# WS2811ControlBoard.net
KiCad netlist of a schematic drawn in EAGLE
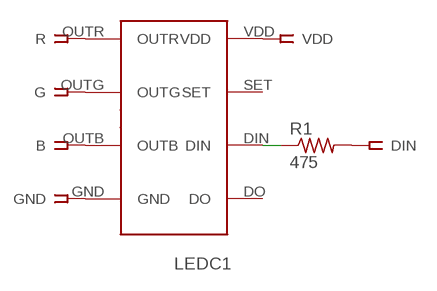
[diagram p0: schematic, sheet 1]

(export (version "E")
  (design (tool "Eeschema 10.0.6"))
  (components
    (comp (ref "B")
      (value "SSW-101-02-G-S")
      (footprint "eagle-import:SSW-101-02-G-S")
      (fields (field (name "MF") "Samtec Inc."))
      (libsource (lib "eagle-import") (part "SSW-101-02-G-S"))
    )
    (comp (ref "DIN")
      (value "SSW-101-02-G-S")
      (footprint "eagle-import:SSW-101-02-G-S")
      (fields (field (name "MF") "Samtec Inc."))
      (libsource (lib "eagle-import") (part "SSW-101-02-G-S"))
    )
    (comp (ref "G")
      (value "SSW-101-02-G-S")
      (footprint "eagle-import:SSW-101-02-G-S")
      (fields (field (name "MF") "Samtec Inc."))
      (libsource (lib "eagle-import") (part "SSW-101-02-G-S"))
    )
    (comp (ref "GND")
      (value "SSW-101-02-G-S")
      (footprint "eagle-import:SSW-101-02-G-S")
      (fields (field (name "MF") "Samtec Inc."))
      (libsource (lib "eagle-import") (part "SSW-101-02-G-S"))
    )
    (comp (ref "LEDC1")
      (value "WS2811")
      (footprint "eagle-import:SOP8")
      (libsource (lib "eagle-import") (part "WS2811"))
    )
    (comp (ref "R")
      (value "SSW-101-02-G-S")
      (footprint "eagle-import:SSW-101-02-G-S")
      (fields (field (name "MF") "Samtec Inc."))
      (libsource (lib "eagle-import") (part "SSW-101-02-G-S"))
    )
    (comp (ref "R1")
      (value "475")
      (footprint "eagle-import:R0805W")
      (libsource (lib "eagle-import") (part "R-US_R0805W"))
    )
    (comp (ref "VDD")
      (value "SSW-101-02-G-S")
      (footprint "eagle-import:SSW-101-02-G-S")
      (fields (field (name "MF") "Samtec Inc."))
      (libsource (lib "eagle-import") (part "SSW-101-02-G-S"))
    )
  )
  (nets
    (net (code "1") (name "Net-(B-Pad1)") (class "Default")
      (node (ref "B") (pin "1") (pinfunction "1_1") (pintype "passive"))
      (node (ref "LEDC1") (pin "OUTB") (pinfunction "OUTB_OUTB") (pintype "bidirectional"))
    )
    (net (code "2") (name "Net-(DIN-Pad1)") (class "Default")
      (node (ref "DIN") (pin "1") (pinfunction "1_1") (pintype "passive"))
      (node (ref "R1") (pin "2") (pinfunction "2_2") (pintype "passive"))
    )
    (net (code "3") (name "Net-(G-Pad1)") (class "Default")
      (node (ref "G") (pin "1") (pinfunction "1_1") (pintype "passive"))
      (node (ref "LEDC1") (pin "OUTG") (pinfunction "OUTG_OUTG") (pintype "bidirectional"))
    )
    (net (code "4") (name "Net-(GND-Pad1)") (class "Default")
      (node (ref "GND") (pin "1") (pinfunction "1_1") (pintype "passive"))
      (node (ref "LEDC1") (pin "GND") (pinfunction "GND_GND") (pintype "bidirectional"))
    )
    (net (code "5") (name "Net-(LEDC1-PadDIN)") (class "Default")
      (node (ref "LEDC1") (pin "DIN") (pinfunction "DIN_DIN") (pintype "bidirectional"))
      (node (ref "R1") (pin "1") (pinfunction "1_1") (pintype "passive"))
    )
    (net (code "6") (name "Net-(LEDC1-PadOUTR)") (class "Default")
      (node (ref "LEDC1") (pin "OUTR") (pinfunction "OUTR_OUTR") (pintype "bidirectional"))
      (node (ref "R") (pin "1") (pinfunction "1_1") (pintype "passive"))
    )
    (net (code "7") (name "Net-(LEDC1-PadVDD)") (class "Default")
      (node (ref "LEDC1") (pin "VDD") (pinfunction "VDD_VDD") (pintype "bidirectional"))
      (node (ref "VDD") (pin "1") (pinfunction "1_1") (pintype "passive"))
    )
    (net (code "8") (name "unconnected-(LEDC1-PadDO)") (class "Default")
      (node (ref "LEDC1") (pin "DO") (pinfunction "DO_DO") (pintype "bidirectional"))
    )
    (net (code "9") (name "unconnected-(LEDC1-PadSET)") (class "Default")
      (node (ref "LEDC1") (pin "SET") (pinfunction "SET_SET") (pintype "bidirectional"))
    )
  )
)
